# Steamer_SCH.net
KiCad netlist of a schematic drawn in Altium Designer
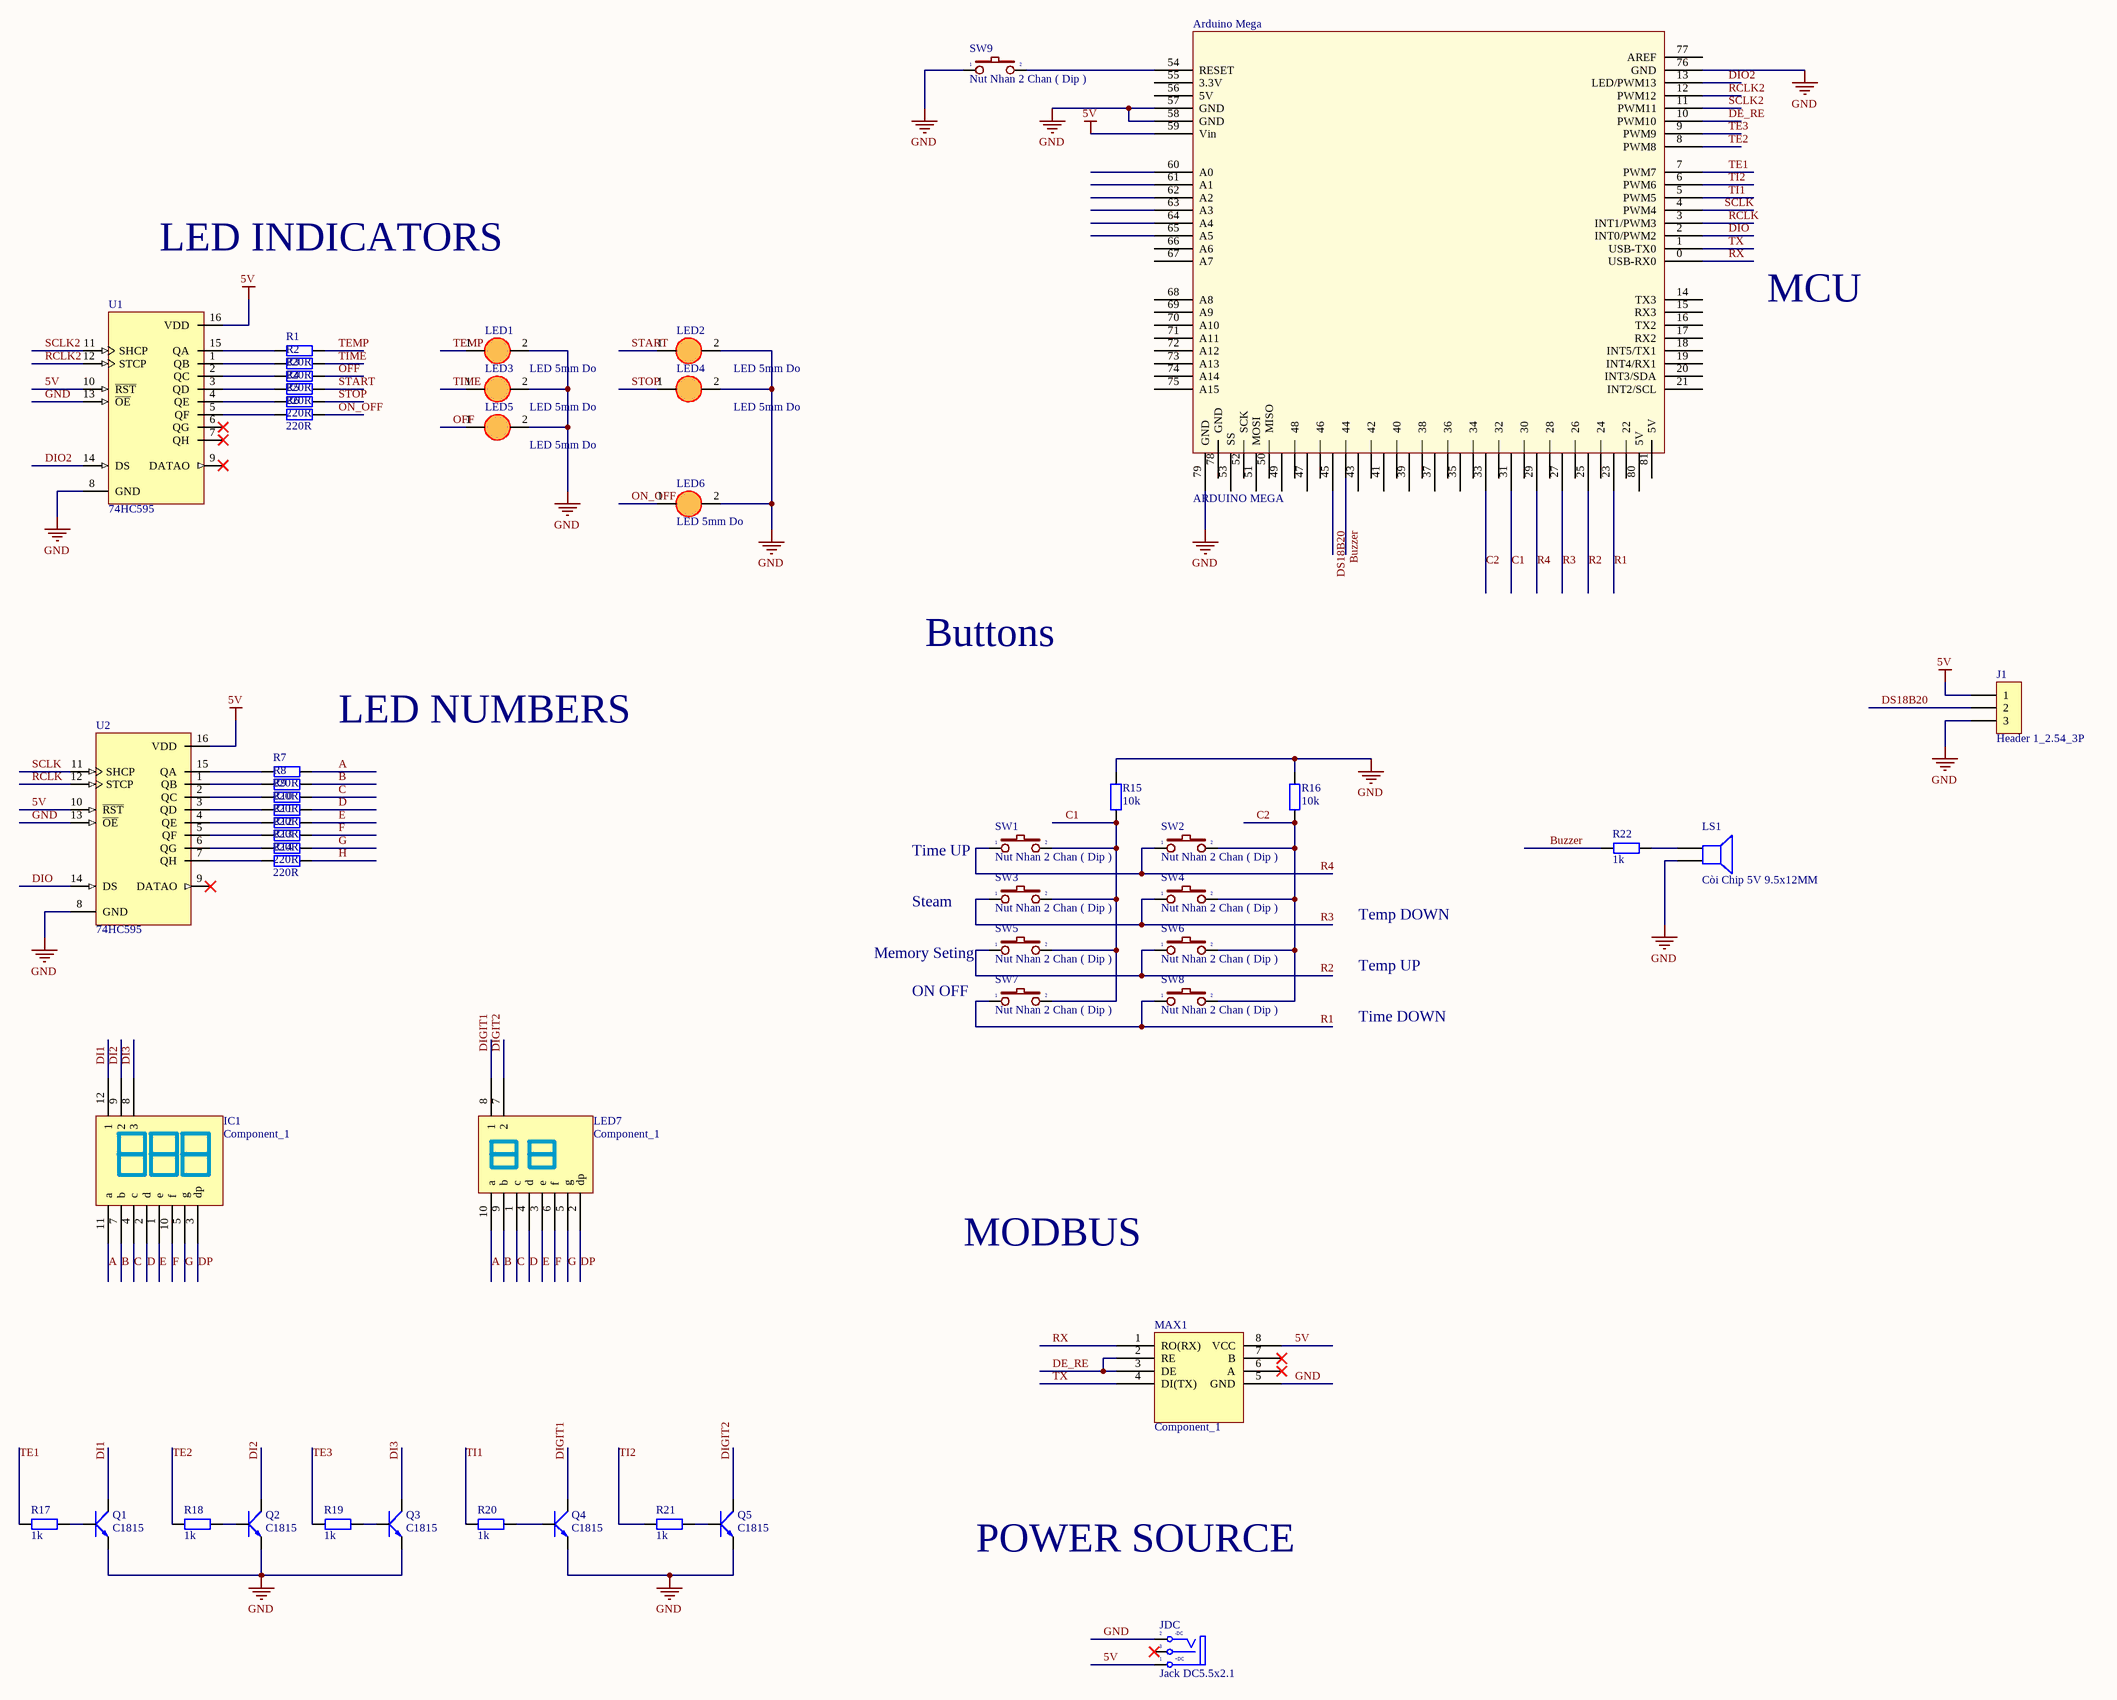
[diagram p0: Steamer_SCH.SchDoc]

(export (version "E")
  (design (tool "Eeschema 10.0.6"))
  (components
    (comp (ref "Arduino Mega")
      (value "ARDUINO MEGA")
      (footprint "ARDUINO MEGA")
      (libsource (lib "Arduino") (part "ARDUINO MEGA"))
    )
    (comp (ref "IC1")
      (value "Component_1")
      (footprint "7SEG_MPX3")
      (description "5631AS LED 7 Segment 3 digits")
      (libsource (lib "5631AS_Lib") (part "Component_1"))
    )
    (comp (ref "J1")
      (value "Header 1_2.54_3P")
      (footprint "Header_Duc Cong_3P 2.54")
      (description "Cắm")
      (libsource (lib "THU VIEN SCH") (part "Header 1_2.54_3P"))
    )
    (comp (ref "JDC")
      (value "Jack DC5.5x2.1")
      (footprint "DC-IN")
      (description "Cắm")
      (libsource (lib "THU VIEN SCH") (part "Jac_DC"))
    )
    (comp (ref "LED1")
      (value "LED 5mm Do")
      (footprint "LED 5mm DO")
      (description "Cắm")
      (libsource (lib "THU VIEN SCH") (part "LED 5mm Do"))
    )
    (comp (ref "LED2")
      (value "LED 5mm Do")
      (footprint "LED 5mm DO")
      (description "Cắm")
      (libsource (lib "THU VIEN SCH") (part "LED 5mm Do"))
    )
    (comp (ref "LED3")
      (value "LED 5mm Do")
      (footprint "LED 5mm DO")
      (description "Cắm")
      (libsource (lib "THU VIEN SCH") (part "LED 5mm Do"))
    )
    (comp (ref "LED4")
      (value "LED 5mm Do")
      (footprint "LED 5mm DO")
      (description "Cắm")
      (libsource (lib "THU VIEN SCH") (part "LED 5mm Do"))
    )
    (comp (ref "LED5")
      (value "LED 5mm Do")
      (footprint "LED 5mm DO")
      (description "Cắm")
      (libsource (lib "THU VIEN SCH") (part "LED 5mm Do"))
    )
    (comp (ref "LED6")
      (value "LED 5mm Do")
      (footprint "LED 5mm DO")
      (description "Cắm")
      (libsource (lib "THU VIEN SCH") (part "LED 5mm Do"))
    )
    (comp (ref "LED7")
      (value "Component_1")
      (footprint "5621AS_Lib")
      (libsource (lib "5621AS_Lib") (part "Component_1"))
    )
    (comp (ref "LS1")
      (value "Còi Chip 5V 9.5x12MM")
      (footprint "SPK")
      (description "Cắm")
      (libsource (lib "THU VIEN SCH") (part "Coi Chip 5V"))
    )
    (comp (ref "MAX1")
      (value "Component_1")
      (footprint "MAX485_Module")
      (libsource (lib "MAX485_Module_Lib") (part "Component_1"))
    )
    (comp (ref "Q1")
      (value "C1815")
      (footprint "QTO-92")
      (description "Dán")
      (libsource (lib "THU VIEN SCH") (part "C1815"))
    )
    (comp (ref "Q2")
      (value "C1815")
      (footprint "QTO-92")
      (description "Dán")
      (libsource (lib "THU VIEN SCH") (part "C1815"))
    )
    (comp (ref "Q3")
      (value "C1815")
      (footprint "QTO-92")
      (description "Dán")
      (libsource (lib "THU VIEN SCH") (part "C1815"))
    )
    (comp (ref "Q4")
      (value "C1815")
      (footprint "QTO-92")
      (description "Dán")
      (libsource (lib "THU VIEN SCH") (part "C1815"))
    )
    (comp (ref "Q5")
      (value "C1815")
      (footprint "QTO-92")
      (description "Dán")
      (libsource (lib "THU VIEN SCH") (part "C1815"))
    )
    (comp (ref "R1")
      (value "220R")
      (footprint "tro vach 1/4w")
      (description "Cắm")
      (libsource (lib "THU VIEN SCH") (part "Tro Vach 1/4W 5% 220R"))
    )
    (comp (ref "R2")
      (value "220R")
      (footprint "tro vach 1/4w")
      (description "Cắm")
      (libsource (lib "THU VIEN SCH") (part "Tro Vach 1/4W 5% 220R"))
    )
    (comp (ref "R3")
      (value "220R")
      (footprint "tro vach 1/4w")
      (description "Cắm")
      (libsource (lib "THU VIEN SCH") (part "Tro Vach 1/4W 5% 220R"))
    )
    (comp (ref "R4")
      (value "220R")
      (footprint "tro vach 1/4w")
      (description "Cắm")
      (libsource (lib "THU VIEN SCH") (part "Tro Vach 1/4W 5% 220R"))
    )
    (comp (ref "R5")
      (value "220R")
      (footprint "tro vach 1/4w")
      (description "Cắm")
      (libsource (lib "THU VIEN SCH") (part "Tro Vach 1/4W 5% 220R"))
    )
    (comp (ref "R6")
      (value "220R")
      (footprint "tro vach 1/4w")
      (description "Cắm")
      (libsource (lib "THU VIEN SCH") (part "Tro Vach 1/4W 5% 220R"))
    )
    (comp (ref "R7")
      (value "220R")
      (footprint "tro vach 1/4w")
      (description "Cắm")
      (libsource (lib "THU VIEN SCH") (part "Tro Vach 1/4W 5% 220R"))
    )
    (comp (ref "R8")
      (value "220R")
      (footprint "tro vach 1/4w")
      (description "Cắm")
      (libsource (lib "THU VIEN SCH") (part "Tro Vach 1/4W 5% 220R"))
    )
    (comp (ref "R9")
      (value "220R")
      (footprint "tro vach 1/4w")
      (description "Cắm")
      (libsource (lib "THU VIEN SCH") (part "Tro Vach 1/4W 5% 220R"))
    )
    (comp (ref "R10")
      (value "220R")
      (footprint "tro vach 1/4w")
      (description "Cắm")
      (libsource (lib "THU VIEN SCH") (part "Tro Vach 1/4W 5% 220R"))
    )
    (comp (ref "R11")
      (value "220R")
      (footprint "tro vach 1/4w")
      (description "Cắm")
      (libsource (lib "THU VIEN SCH") (part "Tro Vach 1/4W 5% 220R"))
    )
    (comp (ref "R12")
      (value "220R")
      (footprint "tro vach 1/4w")
      (description "Cắm")
      (libsource (lib "THU VIEN SCH") (part "Tro Vach 1/4W 5% 220R"))
    )
    (comp (ref "R13")
      (value "220R")
      (footprint "tro vach 1/4w")
      (description "Cắm")
      (libsource (lib "THU VIEN SCH") (part "Tro Vach 1/4W 5% 220R"))
    )
    (comp (ref "R14")
      (value "220R")
      (footprint "tro vach 1/4w")
      (description "Cắm")
      (libsource (lib "THU VIEN SCH") (part "Tro Vach 1/4W 5% 220R"))
    )
    (comp (ref "R15")
      (value "10k")
      (footprint "tro vach 1/4w")
      (description "Căm")
      (libsource (lib "THU VIEN SCH") (part "Tro Vach 1/4W 5% 10k"))
    )
    (comp (ref "R16")
      (value "10k")
      (footprint "tro vach 1/4w")
      (description "Căm")
      (libsource (lib "THU VIEN SCH") (part "Tro Vach 1/4W 5% 10k"))
    )
    (comp (ref "R17")
      (value "1k")
      (footprint "tro vach 1/4w")
      (description "Cắm")
      (libsource (lib "THU VIEN SCH") (part "Tro Vach 1/4W 5% 1k"))
    )
    (comp (ref "R18")
      (value "1k")
      (footprint "tro vach 1/4w")
      (description "Cắm")
      (libsource (lib "THU VIEN SCH") (part "Tro Vach 1/4W 5% 1k"))
    )
    (comp (ref "R19")
      (value "1k")
      (footprint "tro vach 1/4w")
      (description "Cắm")
      (libsource (lib "THU VIEN SCH") (part "Tro Vach 1/4W 5% 1k"))
    )
    (comp (ref "R20")
      (value "1k")
      (footprint "tro vach 1/4w")
      (description "Cắm")
      (libsource (lib "THU VIEN SCH") (part "Tro Vach 1/4W 5% 1k"))
    )
    (comp (ref "R21")
      (value "1k")
      (footprint "tro vach 1/4w")
      (description "Cắm")
      (libsource (lib "THU VIEN SCH") (part "Tro Vach 1/4W 5% 1k"))
    )
    (comp (ref "R22")
      (value "1k")
      (footprint "tro vach 1/4w")
      (description "Cắm")
      (libsource (lib "THU VIEN SCH") (part "Tro Vach 1/4W 5% 1k"))
    )
    (comp (ref "SW1")
      (value "Nut Nhan 2 Chan ( Dip )")
      (footprint "SW2")
      (description "Cắm")
      (libsource (lib "THU VIEN SCH") (part "Nut Nhan 2 Chan ( Dip )"))
    )
    (comp (ref "SW2")
      (value "Nut Nhan 2 Chan ( Dip )")
      (footprint "SW2")
      (description "Cắm")
      (libsource (lib "THU VIEN SCH") (part "Nut Nhan 2 Chan ( Dip )"))
    )
    (comp (ref "SW3")
      (value "Nut Nhan 2 Chan ( Dip )")
      (footprint "SW2")
      (description "Cắm")
      (libsource (lib "THU VIEN SCH") (part "Nut Nhan 2 Chan ( Dip )"))
    )
    (comp (ref "SW4")
      (value "Nut Nhan 2 Chan ( Dip )")
      (footprint "SW2")
      (description "Cắm")
      (libsource (lib "THU VIEN SCH") (part "Nut Nhan 2 Chan ( Dip )"))
    )
    (comp (ref "SW5")
      (value "Nut Nhan 2 Chan ( Dip )")
      (footprint "SW2")
      (description "Cắm")
      (libsource (lib "THU VIEN SCH") (part "Nut Nhan 2 Chan ( Dip )"))
    )
    (comp (ref "SW6")
      (value "Nut Nhan 2 Chan ( Dip )")
      (footprint "SW2")
      (description "Cắm")
      (libsource (lib "THU VIEN SCH") (part "Nut Nhan 2 Chan ( Dip )"))
    )
    (comp (ref "SW7")
      (value "Nut Nhan 2 Chan ( Dip )")
      (footprint "SW2")
      (description "Cắm")
      (libsource (lib "THU VIEN SCH") (part "Nut Nhan 2 Chan ( Dip )"))
    )
    (comp (ref "SW8")
      (value "Nut Nhan 2 Chan ( Dip )")
      (footprint "SW2")
      (description "Cắm")
      (libsource (lib "THU VIEN SCH") (part "Nut Nhan 2 Chan ( Dip )"))
    )
    (comp (ref "SW9")
      (value "Nut Nhan 2 Chan ( Dip )")
      (footprint "SW2")
      (description "Cắm")
      (libsource (lib "THU VIEN SCH") (part "Nut Nhan 2 Chan ( Dip )"))
    )
    (comp (ref "U1")
      (value "74HC595")
      (footprint "DIP16/W0.3")
      (description "Dán")
      (libsource (lib "THU VIEN SCH") (part "74HC595"))
    )
    (comp (ref "U2")
      (value "74HC595")
      (footprint "DIP16/W0.3")
      (description "Dán")
      (libsource (lib "THU VIEN SCH") (part "74HC595"))
    )
  )
  (nets
    (net (code "1") (name "/A") (class "Default")
      (node (ref "IC1") (pin "11") (pinfunction "a_11") (pintype "passive"))
      (node (ref "LED7") (pin "10") (pinfunction "a_10") (pintype "passive"))
      (node (ref "R7") (pin "2") (pinfunction "2_2") (pintype "passive"))
    )
    (net (code "2") (name "/B") (class "Default")
      (node (ref "IC1") (pin "7") (pinfunction "b_7") (pintype "passive"))
      (node (ref "LED7") (pin "9") (pinfunction "b_9") (pintype "passive"))
      (node (ref "R8") (pin "2") (pinfunction "2_2") (pintype "passive"))
    )
    (net (code "3") (name "/Buzzer") (class "Default")
      (node (ref "Arduino Mega") (pin "44") (pinfunction "44_44") (pintype "passive"))
      (node (ref "R22") (pin "1") (pinfunction "1_1") (pintype "passive"))
    )
    (net (code "4") (name "/C") (class "Default")
      (node (ref "IC1") (pin "4") (pinfunction "c_4") (pintype "passive"))
      (node (ref "LED7") (pin "1") (pinfunction "c_1") (pintype "passive"))
      (node (ref "R9") (pin "2") (pinfunction "2_2") (pintype "passive"))
    )
    (net (code "5") (name "/C1") (class "Default")
      (node (ref "Arduino Mega") (pin "31") (pinfunction "31_31") (pintype "passive"))
      (node (ref "R15") (pin "1") (pinfunction "1_1") (pintype "passive"))
      (node (ref "SW1") (pin "2") (pinfunction "2_2") (pintype "passive"))
      (node (ref "SW3") (pin "2") (pinfunction "2_2") (pintype "passive"))
      (node (ref "SW5") (pin "2") (pinfunction "2_2") (pintype "passive"))
      (node (ref "SW7") (pin "2") (pinfunction "2_2") (pintype "passive"))
    )
    (net (code "6") (name "/C2") (class "Default")
      (node (ref "Arduino Mega") (pin "33") (pinfunction "33_33") (pintype "passive"))
      (node (ref "R16") (pin "1") (pinfunction "1_1") (pintype "passive"))
      (node (ref "SW2") (pin "2") (pinfunction "2_2") (pintype "passive"))
      (node (ref "SW4") (pin "2") (pinfunction "2_2") (pintype "passive"))
      (node (ref "SW6") (pin "2") (pinfunction "2_2") (pintype "passive"))
      (node (ref "SW8") (pin "2") (pinfunction "2_2") (pintype "passive"))
    )
    (net (code "7") (name "/D") (class "Default")
      (node (ref "IC1") (pin "2") (pinfunction "d_2") (pintype "passive"))
      (node (ref "LED7") (pin "4") (pinfunction "d_4") (pintype "passive"))
      (node (ref "R10") (pin "2") (pinfunction "2_2") (pintype "passive"))
    )
    (net (code "8") (name "/DE_RE") (class "Default")
      (node (ref "Arduino Mega") (pin "10") (pinfunction "PWM10_10") (pintype "passive"))
      (node (ref "MAX1") (pin "2") (pinfunction "RE_2") (pintype "passive"))
      (node (ref "MAX1") (pin "3") (pinfunction "DE_3") (pintype "passive"))
    )
    (net (code "9") (name "/DI1") (class "Default")
      (node (ref "IC1") (pin "12") (pinfunction "1_12") (pintype "passive"))
      (node (ref "Q1") (pin "2") (pinfunction "C_2") (pintype "passive"))
    )
    (net (code "10") (name "/DI2") (class "Default")
      (node (ref "IC1") (pin "9") (pinfunction "2_9") (pintype "passive"))
      (node (ref "Q2") (pin "2") (pinfunction "C_2") (pintype "passive"))
    )
    (net (code "11") (name "/DI3") (class "Default")
      (node (ref "IC1") (pin "8") (pinfunction "3_8") (pintype "passive"))
      (node (ref "Q3") (pin "2") (pinfunction "C_2") (pintype "passive"))
    )
    (net (code "12") (name "/DIGIT1") (class "Default")
      (node (ref "LED7") (pin "8") (pinfunction "1_8") (pintype "passive"))
      (node (ref "Q4") (pin "2") (pinfunction "C_2") (pintype "passive"))
    )
    (net (code "13") (name "/DIGIT2") (class "Default")
      (node (ref "LED7") (pin "7") (pinfunction "2_7") (pintype "passive"))
      (node (ref "Q5") (pin "2") (pinfunction "C_2") (pintype "passive"))
    )
    (net (code "14") (name "/DIO") (class "Default")
      (node (ref "Arduino Mega") (pin "2") (pinfunction "INT0/PWM2_2") (pintype "passive"))
      (node (ref "U2") (pin "14") (pinfunction "DS_14") (pintype "input"))
    )
    (net (code "15") (name "/DIO2") (class "Default")
      (node (ref "Arduino Mega") (pin "13") (pinfunction "LED/PWM13_13") (pintype "passive"))
      (node (ref "U1") (pin "14") (pinfunction "DS_14") (pintype "input"))
    )
    (net (code "16") (name "/DP") (class "Default")
      (node (ref "IC1") (pin "3") (pinfunction "dp_3") (pintype "passive"))
      (node (ref "LED7") (pin "2") (pinfunction "dp_2") (pintype "passive"))
    )
    (net (code "17") (name "/DS18B20") (class "Default")
      (node (ref "Arduino Mega") (pin "45") (pinfunction "45_45") (pintype "passive"))
      (node (ref "J1") (pin "2") (pinfunction "2_2") (pintype "passive"))
    )
    (net (code "18") (name "/E") (class "Default")
      (node (ref "IC1") (pin "1") (pinfunction "e_1") (pintype "passive"))
      (node (ref "LED7") (pin "3") (pinfunction "e_3") (pintype "passive"))
      (node (ref "R11") (pin "2") (pinfunction "2_2") (pintype "passive"))
    )
    (net (code "19") (name "/F") (class "Default")
      (node (ref "IC1") (pin "10") (pinfunction "f_10") (pintype "passive"))
      (node (ref "LED7") (pin "6") (pinfunction "f_6") (pintype "passive"))
      (node (ref "R12") (pin "2") (pinfunction "2_2") (pintype "passive"))
    )
    (net (code "20") (name "/G") (class "Default")
      (node (ref "IC1") (pin "5") (pinfunction "g_5") (pintype "passive"))
      (node (ref "LED7") (pin "5") (pinfunction "g_5") (pintype "passive"))
      (node (ref "R13") (pin "2") (pinfunction "2_2") (pintype "passive"))
    )
    (net (code "21") (name "/H") (class "Default")
      (node (ref "R14") (pin "2") (pinfunction "2_2") (pintype "passive"))
    )
    (net (code "22") (name "/OFF") (class "Default")
      (node (ref "LED5") (pin "1") (pinfunction "A_1") (pintype "passive"))
      (node (ref "R3") (pin "2") (pinfunction "2_2") (pintype "passive"))
    )
    (net (code "23") (name "/ON_OFF") (class "Default")
      (node (ref "LED6") (pin "1") (pinfunction "A_1") (pintype "passive"))
      (node (ref "R6") (pin "2") (pinfunction "2_2") (pintype "passive"))
    )
    (net (code "24") (name "/R1") (class "Default")
      (node (ref "Arduino Mega") (pin "23") (pinfunction "23_23") (pintype "passive"))
      (node (ref "SW7") (pin "1") (pinfunction "1_1") (pintype "passive"))
      (node (ref "SW8") (pin "1") (pinfunction "1_1") (pintype "passive"))
    )
    (net (code "25") (name "/R2") (class "Default")
      (node (ref "Arduino Mega") (pin "25") (pinfunction "25_25") (pintype "passive"))
      (node (ref "SW5") (pin "1") (pinfunction "1_1") (pintype "passive"))
      (node (ref "SW6") (pin "1") (pinfunction "1_1") (pintype "passive"))
    )
    (net (code "26") (name "/R3") (class "Default")
      (node (ref "Arduino Mega") (pin "27") (pinfunction "27_27") (pintype "passive"))
      (node (ref "SW3") (pin "1") (pinfunction "1_1") (pintype "passive"))
      (node (ref "SW4") (pin "1") (pinfunction "1_1") (pintype "passive"))
    )
    (net (code "27") (name "/R4") (class "Default")
      (node (ref "Arduino Mega") (pin "29") (pinfunction "29_29") (pintype "passive"))
      (node (ref "SW1") (pin "1") (pinfunction "1_1") (pintype "passive"))
      (node (ref "SW2") (pin "1") (pinfunction "1_1") (pintype "passive"))
    )
    (net (code "28") (name "/RCLK") (class "Default")
      (node (ref "Arduino Mega") (pin "3") (pinfunction "INT1/PWM3_3") (pintype "passive"))
      (node (ref "U2") (pin "12") (pinfunction "STCP_12") (pintype "input"))
    )
    (net (code "29") (name "/RCLK2") (class "Default")
      (node (ref "Arduino Mega") (pin "12") (pinfunction "PWM12_12") (pintype "passive"))
      (node (ref "U1") (pin "12") (pinfunction "STCP_12") (pintype "input"))
    )
    (net (code "30") (name "/RX") (class "Default")
      (node (ref "Arduino Mega") (pin "0") (pinfunction "USB-RX0_0") (pintype "passive"))
      (node (ref "MAX1") (pin "1") (pinfunction "RO(RX)_1") (pintype "passive"))
    )
    (net (code "31") (name "/SCLK") (class "Default")
      (node (ref "Arduino Mega") (pin "4") (pinfunction "PWM4_4") (pintype "passive"))
      (node (ref "U2") (pin "11") (pinfunction "SHCP_11") (pintype "input"))
    )
    (net (code "32") (name "/SCLK2") (class "Default")
      (node (ref "Arduino Mega") (pin "11") (pinfunction "PWM11_11") (pintype "passive"))
      (node (ref "U1") (pin "11") (pinfunction "SHCP_11") (pintype "input"))
    )
    (net (code "33") (name "/START") (class "Default")
      (node (ref "LED2") (pin "1") (pinfunction "A_1") (pintype "passive"))
      (node (ref "R4") (pin "2") (pinfunction "2_2") (pintype "passive"))
    )
    (net (code "34") (name "/STOP") (class "Default")
      (node (ref "LED4") (pin "1") (pinfunction "A_1") (pintype "passive"))
      (node (ref "R5") (pin "2") (pinfunction "2_2") (pintype "passive"))
    )
    (net (code "35") (name "/TE1") (class "Default")
      (node (ref "Arduino Mega") (pin "7") (pinfunction "PWM7_7") (pintype "passive"))
      (node (ref "R17") (pin "1") (pinfunction "1_1") (pintype "passive"))
    )
    (net (code "36") (name "/TE2") (class "Default")
      (node (ref "Arduino Mega") (pin "8") (pinfunction "PWM8_8") (pintype "passive"))
      (node (ref "R18") (pin "1") (pinfunction "1_1") (pintype "passive"))
    )
    (net (code "37") (name "/TE3") (class "Default")
      (node (ref "Arduino Mega") (pin "9") (pinfunction "PWM9_9") (pintype "passive"))
      (node (ref "R19") (pin "1") (pinfunction "1_1") (pintype "passive"))
    )
    (net (code "38") (name "/TEMP") (class "Default")
      (node (ref "LED1") (pin "1") (pinfunction "A_1") (pintype "passive"))
      (node (ref "R1") (pin "2") (pinfunction "2_2") (pintype "passive"))
    )
    (net (code "39") (name "/TI1") (class "Default")
      (node (ref "Arduino Mega") (pin "5") (pinfunction "PWM5_5") (pintype "passive"))
      (node (ref "R20") (pin "1") (pinfunction "1_1") (pintype "passive"))
    )
    (net (code "40") (name "/TI2") (class "Default")
      (node (ref "Arduino Mega") (pin "6") (pinfunction "PWM6_6") (pintype "passive"))
      (node (ref "R21") (pin "1") (pinfunction "1_1") (pintype "passive"))
    )
    (net (code "41") (name "/TIME") (class "Default")
      (node (ref "LED3") (pin "1") (pinfunction "A_1") (pintype "passive"))
      (node (ref "R2") (pin "2") (pinfunction "2_2") (pintype "passive"))
    )
    (net (code "42") (name "/TX") (class "Default")
      (node (ref "Arduino Mega") (pin "1") (pinfunction "USB-TX0_1") (pintype "passive"))
      (node (ref "MAX1") (pin "4") (pinfunction "DI(TX)_4") (pintype "passive"))
    )
    (net (code "43") (name "5V") (class "Default")
      (node (ref "Arduino Mega") (pin "59") (pinfunction "Vin_59") (pintype "passive"))
      (node (ref "J1") (pin "1") (pinfunction "1_1") (pintype "passive"))
      (node (ref "JDC") (pin "1") (pinfunction "T_1") (pintype "passive"))
      (node (ref "MAX1") (pin "8") (pinfunction "VCC_8") (pintype "passive"))
      (node (ref "U1") (pin "10") (pinfunction "~{RST}_10") (pintype "input"))
      (node (ref "U1") (pin "16") (pinfunction "VDD_16") (pintype "power_in"))
      (node (ref "U2") (pin "10") (pinfunction "~{RST}_10") (pintype "input"))
      (node (ref "U2") (pin "16") (pinfunction "VDD_16") (pintype "power_in"))
    )
    (net (code "44") (name "GND") (class "Default")
      (node (ref "Arduino Mega") (pin "57") (pinfunction "GND_57") (pintype "passive"))
      (node (ref "Arduino Mega") (pin "58") (pinfunction "GND_58") (pintype "passive"))
      (node (ref "Arduino Mega") (pin "76") (pinfunction "GND_76") (pintype "passive"))
      (node (ref "Arduino Mega") (pin "79") (pinfunction "GND_79") (pintype "passive"))
      (node (ref "J1") (pin "3") (pinfunction "3_3") (pintype "passive"))
      (node (ref "JDC") (pin "2") (pinfunction "TN_2") (pintype "passive"))
      (node (ref "LED1") (pin "2") (pinfunction "K_2") (pintype "passive"))
      (node (ref "LED2") (pin "2") (pinfunction "K_2") (pintype "passive"))
      (node (ref "LED3") (pin "2") (pinfunction "K_2") (pintype "passive"))
      (node (ref "LED4") (pin "2") (pinfunction "K_2") (pintype "passive"))
      (node (ref "LED5") (pin "2") (pinfunction "K_2") (pintype "passive"))
      (node (ref "LED6") (pin "2") (pinfunction "K_2") (pintype "passive"))
      (node (ref "LS1") (pin "2") (pinfunction "2_2") (pintype "passive"))
      (node (ref "MAX1") (pin "5") (pinfunction "GND_5") (pintype "passive"))
      (node (ref "Q1") (pin "3") (pinfunction "E_3") (pintype "passive"))
      (node (ref "Q2") (pin "3") (pinfunction "E_3") (pintype "passive"))
      (node (ref "Q3") (pin "3") (pinfunction "E_3") (pintype "passive"))
      (node (ref "Q4") (pin "3") (pinfunction "E_3") (pintype "passive"))
      (node (ref "Q5") (pin "3") (pinfunction "E_3") (pintype "passive"))
      (node (ref "R15") (pin "2") (pinfunction "2_2") (pintype "passive"))
      (node (ref "R16") (pin "2") (pinfunction "2_2") (pintype "passive"))
      (node (ref "SW9") (pin "1") (pinfunction "1_1") (pintype "passive"))
      (node (ref "U1") (pin "13") (pinfunction "~{OE}_13") (pintype "input"))
      (node (ref "U1") (pin "8") (pinfunction "GND_8") (pintype "power_in"))
      (node (ref "U2") (pin "13") (pinfunction "~{OE}_13") (pintype "input"))
      (node (ref "U2") (pin "8") (pinfunction "GND_8") (pintype "power_in"))
    )
    (net (code "45") (name "Net-(Arduino Mega-RESET)") (class "Default")
      (node (ref "Arduino Mega") (pin "54") (pinfunction "RESET_54") (pintype "passive"))
      (node (ref "SW9") (pin "2") (pinfunction "2_2") (pintype "passive"))
    )
    (net (code "46") (name "Net-(LS1-Pad1)") (class "Default")
      (node (ref "LS1") (pin "1") (pinfunction "1_1") (pintype "passive"))
      (node (ref "R22") (pin "2") (pinfunction "2_2") (pintype "passive"))
    )
    (net (code "47") (name "Net-(Q1-B)") (class "Default")
      (node (ref "Q1") (pin "1") (pinfunction "B_1") (pintype "passive"))
      (node (ref "R17") (pin "2") (pinfunction "2_2") (pintype "passive"))
    )
    (net (code "48") (name "Net-(Q2-B)") (class "Default")
      (node (ref "Q2") (pin "1") (pinfunction "B_1") (pintype "passive"))
      (node (ref "R18") (pin "2") (pinfunction "2_2") (pintype "passive"))
    )
    (net (code "49") (name "Net-(Q3-B)") (class "Default")
      (node (ref "Q3") (pin "1") (pinfunction "B_1") (pintype "passive"))
      (node (ref "R19") (pin "2") (pinfunction "2_2") (pintype "passive"))
    )
    (net (code "50") (name "Net-(Q4-B)") (class "Default")
      (node (ref "Q4") (pin "1") (pinfunction "B_1") (pintype "passive"))
      (node (ref "R20") (pin "2") (pinfunction "2_2") (pintype "passive"))
    )
    (net (code "51") (name "Net-(Q5-B)") (class "Default")
      (node (ref "Q5") (pin "1") (pinfunction "B_1") (pintype "passive"))
      (node (ref "R21") (pin "2") (pinfunction "2_2") (pintype "passive"))
    )
    (net (code "52") (name "Net-(U1-QA)") (class "Default")
      (node (ref "R1") (pin "1") (pinfunction "1_1") (pintype "passive"))
      (node (ref "U1") (pin "15") (pinfunction "QA_15") (pintype "tri_state"))
    )
    (net (code "53") (name "Net-(U1-QB)") (class "Default")
      (node (ref "R2") (pin "1") (pinfunction "1_1") (pintype "passive"))
      (node (ref "U1") (pin "1") (pinfunction "QB_1") (pintype "tri_state"))
    )
    (net (code "54") (name "Net-(U1-QC)") (class "Default")
      (node (ref "R3") (pin "1") (pinfunction "1_1") (pintype "passive"))
      (node (ref "U1") (pin "2") (pinfunction "QC_2") (pintype "tri_state"))
    )
    (net (code "55") (name "Net-(U1-QD)") (class "Default")
      (node (ref "R4") (pin "1") (pinfunction "1_1") (pintype "passive"))
      (node (ref "U1") (pin "3") (pinfunction "QD_3") (pintype "tri_state"))
    )
    (net (code "56") (name "Net-(U1-QE)") (class "Default")
      (node (ref "R5") (pin "1") (pinfunction "1_1") (pintype "passive"))
      (node (ref "U1") (pin "4") (pinfunction "QE_4") (pintype "tri_state"))
    )
    (net (code "57") (name "Net-(U1-QF)") (class "Default")
      (node (ref "R6") (pin "1") (pinfunction "1_1") (pintype "passive"))
      (node (ref "U1") (pin "5") (pinfunction "QF_5") (pintype "tri_state"))
    )
    (net (code "58") (name "Net-(U2-QA)") (class "Default")
      (node (ref "R7") (pin "1") (pinfunction "1_1") (pintype "passive"))
      (node (ref "U2") (pin "15") (pinfunction "QA_15") (pintype "tri_state"))
    )
    (net (code "59") (name "Net-(U2-QB)") (class "Default")
      (node (ref "R8") (pin "1") (pinfunction "1_1") (pintype "passive"))
      (node (ref "U2") (pin "1") (pinfunction "QB_1") (pintype "tri_state"))
    )
    (net (code "60") (name "Net-(U2-QC)") (class "Default")
      (node (ref "R9") (pin "1") (pinfunction "1_1") (pintype "passive"))
      (node (ref "U2") (pin "2") (pinfunction "QC_2") (pintype "tri_state"))
    )
    (net (code "61") (name "Net-(U2-QD)") (class "Default")
      (node (ref "R10") (pin "1") (pinfunction "1_1") (pintype "passive"))
      (node (ref "U2") (pin "3") (pinfunction "QD_3") (pintype "tri_state"))
    )
    (net (code "62") (name "Net-(U2-QE)") (class "Default")
      (node (ref "R11") (pin "1") (pinfunction "1_1") (pintype "passive"))
      (node (ref "U2") (pin "4") (pinfunction "QE_4") (pintype "tri_state"))
    )
    (net (code "63") (name "Net-(U2-QF)") (class "Default")
      (node (ref "R12") (pin "1") (pinfunction "1_1") (pintype "passive"))
      (node (ref "U2") (pin "5") (pinfunction "QF_5") (pintype "tri_state"))
    )
    (net (code "64") (name "Net-(U2-QG)") (class "Default")
      (node (ref "R13") (pin "1") (pinfunction "1_1") (pintype "passive"))
      (node (ref "U2") (pin "6") (pinfunction "QG_6") (pintype "tri_state"))
    )
    (net (code "65") (name "Net-(U2-QH)") (class "Default")
      (node (ref "R14") (pin "1") (pinfunction "1_1") (pintype "passive"))
      (node (ref "U2") (pin "7") (pinfunction "QH_7") (pintype "tri_state"))
    )
    (net (code "66") (name "unconnected-(Arduino Mega-3.3V-Pad55)") (class "Default")
      (node (ref "Arduino Mega") (pin "55") (pinfunction "3.3V_55") (pintype "passive"))
    )
    (net (code "67") (name "unconnected-(Arduino Mega-5V-Pad56)") (class "Default")
      (node (ref "Arduino Mega") (pin "56") (pinfunction "5V_56") (pintype "passive"))
    )
    (net (code "68") (name "unconnected-(Arduino Mega-5V-Pad80)") (class "Default")
      (node (ref "Arduino Mega") (pin "80") (pinfunction "5V_80") (pintype "passive"))
    )
    (net (code "69") (name "unconnected-(Arduino Mega-5V-Pad81)") (class "Default")
      (node (ref "Arduino Mega") (pin "81") (pinfunction "5V_81") (pintype "passive"))
    )
    (net (code "70") (name "unconnected-(Arduino Mega-A0-Pad60)") (class "Default")
      (node (ref "Arduino Mega") (pin "60") (pinfunction "A0_60") (pintype "passive"))
    )
    (net (code "71") (name "unconnected-(Arduino Mega-A1-Pad61)") (class "Default")
      (node (ref "Arduino Mega") (pin "61") (pinfunction "A1_61") (pintype "passive"))
    )
    (net (code "72") (name "unconnected-(Arduino Mega-A2-Pad62)") (class "Default")
      (node (ref "Arduino Mega") (pin "62") (pinfunction "A2_62") (pintype "passive"))
    )
    (net (code "73") (name "unconnected-(Arduino Mega-A3-Pad63)") (class "Default")
      (node (ref "Arduino Mega") (pin "63") (pinfunction "A3_63") (pintype "passive"))
    )
    (net (code "74") (name "unconnected-(Arduino Mega-A4-Pad64)") (class "Default")
      (node (ref "Arduino Mega") (pin "64") (pinfunction "A4_64") (pintype "passive"))
    )
    (net (code "75") (name "unconnected-(Arduino Mega-A5-Pad65)") (class "Default")
      (node (ref "Arduino Mega") (pin "65") (pinfunction "A5_65") (pintype "passive"))
    )
    (net (code "76") (name "unconnected-(Arduino Mega-A6-Pad66)") (class "Default")
      (node (ref "Arduino Mega") (pin "66") (pinfunction "A6_66") (pintype "passive"))
    )
    (net (code "77") (name "unconnected-(Arduino Mega-A7-Pad67)") (class "Default")
      (node (ref "Arduino Mega") (pin "67") (pinfunction "A7_67") (pintype "passive"))
    )
    (net (code "78") (name "unconnected-(Arduino Mega-A8-Pad68)") (class "Default")
      (node (ref "Arduino Mega") (pin "68") (pinfunction "A8_68") (pintype "passive"))
    )
    (net (code "79") (name "unconnected-(Arduino Mega-A9-Pad69)") (class "Default")
      (node (ref "Arduino Mega") (pin "69") (pinfunction "A9_69") (pintype "passive"))
    )
    (net (code "80") (name "unconnected-(Arduino Mega-A10-Pad70)") (class "Default")
      (node (ref "Arduino Mega") (pin "70") (pinfunction "A10_70") (pintype "passive"))
    )
    (net (code "81") (name "unconnected-(Arduino Mega-A11-Pad71)") (class "Default")
      (node (ref "Arduino Mega") (pin "71") (pinfunction "A11_71") (pintype "passive"))
    )
    (net (code "82") (name "unconnected-(Arduino Mega-A12-Pad72)") (class "Default")
      (node (ref "Arduino Mega") (pin "72") (pinfunction "A12_72") (pintype "passive"))
    )
    (net (code "83") (name "unconnected-(Arduino Mega-A13-Pad73)") (class "Default")
      (node (ref "Arduino Mega") (pin "73") (pinfunction "A13_73") (pintype "passive"))
    )
    (net (code "84") (name "unconnected-(Arduino Mega-A14-Pad74)") (class "Default")
      (node (ref "Arduino Mega") (pin "74") (pinfunction "A14_74") (pintype "passive"))
    )
    (net (code "85") (name "unconnected-(Arduino Mega-A15-Pad75)") (class "Default")
      (node (ref "Arduino Mega") (pin "75") (pinfunction "A15_75") (pintype "passive"))
    )
    (net (code "86") (name "unconnected-(Arduino Mega-AREF-Pad77)") (class "Default")
      (node (ref "Arduino Mega") (pin "77") (pinfunction "AREF_77") (pintype "passive"))
    )
    (net (code "87") (name "unconnected-(Arduino Mega-GND-Pad78)") (class "Default")
      (node (ref "Arduino Mega") (pin "78") (pinfunction "GND_78") (pintype "passive"))
    )
    (net (code "88") (name "unconnected-(Arduino Mega-INT2{slash}SCL-Pad21)") (class "Default")
      (node (ref "Arduino Mega") (pin "21") (pinfunction "INT2/SCL_21") (pintype "passive"))
    )
    (net (code "89") (name "unconnected-(Arduino Mega-INT3{slash}SDA-Pad20)") (class "Default")
      (node (ref "Arduino Mega") (pin "20") (pinfunction "INT3/SDA_20") (pintype "passive"))
    )
    (net (code "90") (name "unconnected-(Arduino Mega-INT4{slash}RX1-Pad19)") (class "Default")
      (node (ref "Arduino Mega") (pin "19") (pinfunction "INT4/RX1_19") (pintype "passive"))
    )
    (net (code "91") (name "unconnected-(Arduino Mega-INT5{slash}TX1-Pad18)") (class "Default")
      (node (ref "Arduino Mega") (pin "18") (pinfunction "INT5/TX1_18") (pintype "passive"))
    )
    (net (code "92") (name "unconnected-(Arduino Mega-MISO-Pad50)") (class "Default")
      (node (ref "Arduino Mega") (pin "50") (pinfunction "MISO_50") (pintype "passive"))
    )
    (net (code "93") (name "unconnected-(Arduino Mega-MOSI-Pad51)") (class "Default")
      (node (ref "Arduino Mega") (pin "51") (pinfunction "MOSI_51") (pintype "passive"))
    )
    (net (code "94") (name "unconnected-(Arduino Mega-Pad22)") (class "Default")
      (node (ref "Arduino Mega") (pin "22") (pinfunction "22_22") (pintype "passive"))
    )
    (net (code "95") (name "unconnected-(Arduino Mega-Pad24)") (class "Default")
      (node (ref "Arduino Mega") (pin "24") (pinfunction "24_24") (pintype "passive"))
    )
    (net (code "96") (name "unconnected-(Arduino Mega-Pad26)") (class "Default")
      (node (ref "Arduino Mega") (pin "26") (pinfunction "26_26") (pintype "passive"))
    )
    (net (code "97") (name "unconnected-(Arduino Mega-Pad28)") (class "Default")
      (node (ref "Arduino Mega") (pin "28") (pinfunction "28_28") (pintype "passive"))
    )
    (net (code "98") (name "unconnected-(Arduino Mega-Pad30)") (class "Default")
      (node (ref "Arduino Mega") (pin "30") (pinfunction "30_30") (pintype "passive"))
    )
    (net (code "99") (name "unconnected-(Arduino Mega-Pad32)") (class "Default")
      (node (ref "Arduino Mega") (pin "32") (pinfunction "32_32") (pintype "passive"))
    )
    (net (code "100") (name "unconnected-(Arduino Mega-Pad34)") (class "Default")
      (node (ref "Arduino Mega") (pin "34") (pinfunction "34_34") (pintype "passive"))
    )
    (net (code "101") (name "unconnected-(Arduino Mega-Pad35)") (class "Default")
      (node (ref "Arduino Mega") (pin "35") (pinfunction "35_35") (pintype "passive"))
    )
    (net (code "102") (name "unconnected-(Arduino Mega-Pad36)") (class "Default")
      (node (ref "Arduino Mega") (pin "36") (pinfunction "36_36") (pintype "passive"))
    )
    (net (code "103") (name "unconnected-(Arduino Mega-Pad37)") (class "Default")
      (node (ref "Arduino Mega") (pin "37") (pinfunction "37_37") (pintype "passive"))
    )
    (net (code "104") (name "unconnected-(Arduino Mega-Pad38)") (class "Default")
      (node (ref "Arduino Mega") (pin "38") (pinfunction "38_38") (pintype "passive"))
    )
    (net (code "105") (name "unconnected-(Arduino Mega-Pad39)") (class "Default")
      (node (ref "Arduino Mega") (pin "39") (pinfunction "39_39") (pintype "passive"))
    )
    (net (code "106") (name "unconnected-(Arduino Mega-Pad40)") (class "Default")
      (node (ref "Arduino Mega") (pin "40") (pinfunction "40_40") (pintype "passive"))
    )
    (net (code "107") (name "unconnected-(Arduino Mega-Pad41)") (class "Default")
      (node (ref "Arduino Mega") (pin "41") (pinfunction "41_41") (pintype "passive"))
    )
    (net (code "108") (name "unconnected-(Arduino Mega-Pad42)") (class "Default")
      (node (ref "Arduino Mega") (pin "42") (pinfunction "42_42") (pintype "passive"))
    )
    (net (code "109") (name "unconnected-(Arduino Mega-Pad43)") (class "Default")
      (node (ref "Arduino Mega") (pin "43") (pinfunction "43_43") (pintype "passive"))
    )
    (net (code "110") (name "unconnected-(Arduino Mega-Pad46)") (class "Default")
      (node (ref "Arduino Mega") (pin "46") (pinfunction "46_46") (pintype "passive"))
    )
    (net (code "111") (name "unconnected-(Arduino Mega-Pad47)") (class "Default")
      (node (ref "Arduino Mega") (pin "47") (pinfunction "47_47") (pintype "passive"))
    )
    (net (code "112") (name "unconnected-(Arduino Mega-Pad48)") (class "Default")
      (node (ref "Arduino Mega") (pin "48") (pinfunction "48_48") (pintype "passive"))
    )
    (net (code "113") (name "unconnected-(Arduino Mega-Pad49)") (class "Default")
      (node (ref "Arduino Mega") (pin "49") (pinfunction "49_49") (pintype "passive"))
    )
    (net (code "114") (name "unconnected-(Arduino Mega-RX2-Pad17)") (class "Default")
      (node (ref "Arduino Mega") (pin "17") (pinfunction "RX2_17") (pintype "passive"))
    )
    (net (code "115") (name "unconnected-(Arduino Mega-RX3-Pad15)") (class "Default")
      (node (ref "Arduino Mega") (pin "15") (pinfunction "RX3_15") (pintype "passive"))
    )
    (net (code "116") (name "unconnected-(Arduino Mega-SCK-Pad52)") (class "Default")
      (node (ref "Arduino Mega") (pin "52") (pinfunction "SCK_52") (pintype "passive"))
    )
    (net (code "117") (name "unconnected-(Arduino Mega-SS-Pad53)") (class "Default")
      (node (ref "Arduino Mega") (pin "53") (pinfunction "SS_53") (pintype "passive"))
    )
    (net (code "118") (name "unconnected-(Arduino Mega-TX2-Pad16)") (class "Default")
      (node (ref "Arduino Mega") (pin "16") (pinfunction "TX2_16") (pintype "passive"))
    )
    (net (code "119") (name "unconnected-(Arduino Mega-TX3-Pad14)") (class "Default")
      (node (ref "Arduino Mega") (pin "14") (pinfunction "TX3_14") (pintype "passive"))
    )
    (net (code "120") (name "unconnected-(JDC-S-Pad3)") (class "Default")
      (node (ref "JDC") (pin "3") (pinfunction "S_3") (pintype "power_in+no_connect"))
    )
    (net (code "121") (name "unconnected-(MAX1-A-Pad6)") (class "Default")
      (node (ref "MAX1") (pin "6") (pinfunction "A_6") (pintype "passive+no_connect"))
    )
    (net (code "122") (name "unconnected-(MAX1-B-Pad7)") (class "Default")
      (node (ref "MAX1") (pin "7") (pinfunction "B_7") (pintype "passive+no_connect"))
    )
    (net (code "123") (name "unconnected-(U1-DATAO-Pad9)") (class "Default")
      (node (ref "U1") (pin "9") (pinfunction "DATAO_9") (pintype "output+no_connect"))
    )
    (net (code "124") (name "unconnected-(U1-QG-Pad6)") (class "Default")
      (node (ref "U1") (pin "6") (pinfunction "QG_6") (pintype "tri_state+no_connect"))
    )
    (net (code "125") (name "unconnected-(U1-QH-Pad7)") (class "Default")
      (node (ref "U1") (pin "7") (pinfunction "QH_7") (pintype "tri_state+no_connect"))
    )
    (net (code "126") (name "unconnected-(U2-DATAO-Pad9)") (class "Default")
      (node (ref "U2") (pin "9") (pinfunction "DATAO_9") (pintype "output+no_connect"))
    )
  )
)
